# power.net
KiCad netlist of a schematic drawn in Altium Designer
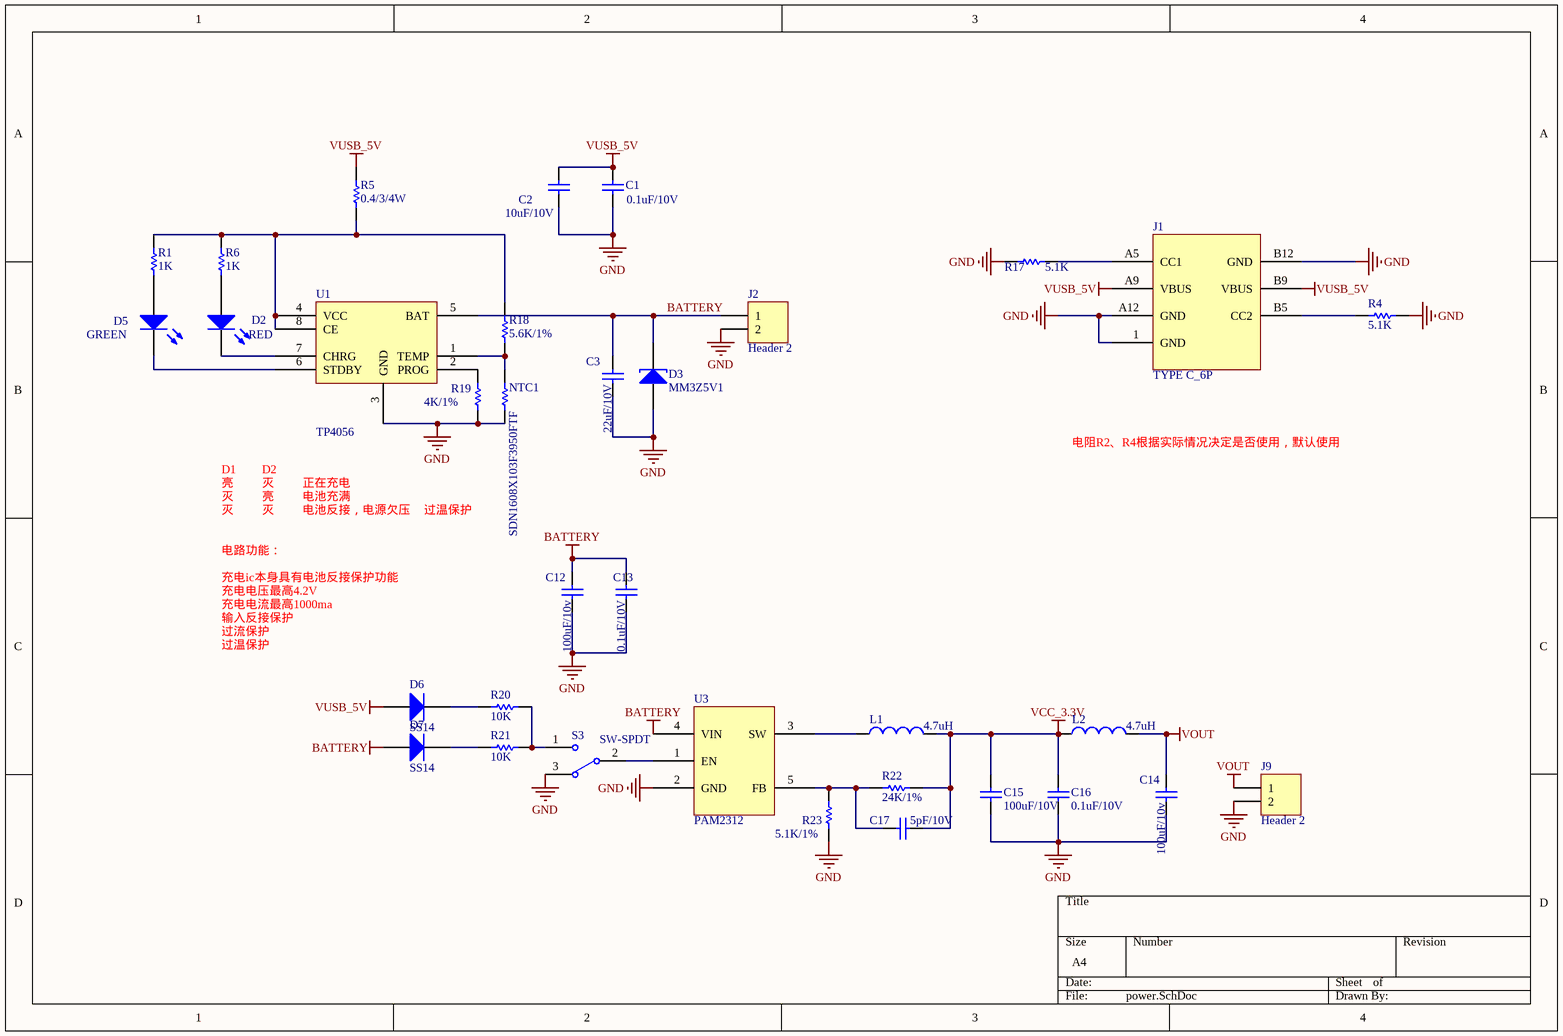
[diagram p0: power.SchDoc]

(export (version "E")
  (design (tool "Eeschema 10.0.6"))
  (components
    (comp (ref "C1")
      (value "0.1uF/10V")
      (footprint "0402C")
      (description "Capacitor")
      (fields (field (name "PUBLISHER") "Altium Limited"))
      (libsource (lib "Miscellaneous Devices") (part "Cap"))
    )
    (comp (ref "C2")
      (value "10uF/10V")
      (footprint "0603C")
      (description "Capacitor")
      (fields (field (name "PUBLISHER") "Altium Limited"))
      (libsource (lib "Miscellaneous Devices") (part "Cap"))
    )
    (comp (ref "C3")
      (value "22uF/10V")
      (footprint "1206C")
      (description "Capacitor")
      (fields (field (name "PUBLISHER") "Altium Limited"))
      (libsource (lib "Miscellaneous Devices") (part "Cap"))
    )
    (comp (ref "C12")
      (value "100uF/10v")
      (footprint "1206C")
      (description "Capacitor")
      (fields (field (name "PUBLISHER") "Altium Limited"))
      (libsource (lib "Miscellaneous Devices") (part "Cap"))
    )
    (comp (ref "C13")
      (value "0.1uF/10V")
      (footprint "0402c")
      (description "Capacitor")
      (fields (field (name "PUBLISHER") "Altium Limited"))
      (libsource (lib "Miscellaneous Devices") (part "Cap"))
    )
    (comp (ref "C14")
      (value "100uF/10v")
      (footprint "1206C")
      (description "Capacitor")
      (fields (field (name "PUBLISHER") "Altium Limited"))
      (libsource (lib "Miscellaneous Devices") (part "Cap"))
    )
    (comp (ref "C15")
      (value "100uF/10V")
      (footprint "1206C")
      (description "Capacitor")
      (fields (field (name "PUBLISHER") "Altium Limited"))
      (libsource (lib "Miscellaneous Devices") (part "Cap"))
    )
    (comp (ref "C16")
      (value "0.1uF/10V")
      (footprint "0402C")
      (description "Capacitor")
      (fields (field (name "PUBLISHER") "Altium Limited"))
      (libsource (lib "Miscellaneous Devices") (part "Cap"))
    )
    (comp (ref "C17")
      (value "5pF/10V")
      (footprint "0402C")
      (description "Capacitor")
      (fields (field (name "PUBLISHER") "Altium Limited"))
      (libsource (lib "Miscellaneous Devices") (part "Cap"))
    )
    (comp (ref "D2")
      (value "~")
      (footprint "0603LED")
      (description "Typical INFRARED GaAs LED")
      (fields (field (name "PUBLISHER") "RED"))
      (libsource (lib "Miscellaneous Devices") (part "LED0"))
    )
    (comp (ref "D3")
      (value "MM3Z5V1")
      (footprint "SOD323")
      (description "Tunnel Diode - RLC Model")
      (fields (field (name "PUBLISHER") "Altium Limited"))
      (libsource (lib "Miscellaneous Devices") (part "D Tunnel1"))
    )
    (comp (ref "D5")
      (value "~")
      (footprint "0603LED")
      (description "Typical INFRARED GaAs LED")
      (fields (field (name "PUBLISHER") "GREEN"))
      (libsource (lib "Miscellaneous Devices") (part "LED0"))
    )
    (comp (ref "D6")
      (value "SS14")
      (footprint "SMA")
      (description "Default Diode")
      (fields (field (name "PUBLISHER") "Altium Limited"))
      (libsource (lib "Miscellaneous Devices") (part "Diode"))
    )
    (comp (ref "D7")
      (value "SS14")
      (footprint "SMA")
      (description "Default Diode")
      (fields (field (name "PUBLISHER") "Altium Limited"))
      (libsource (lib "Miscellaneous Devices") (part "Diode"))
    )
    (comp (ref "J1")
      (value "TYPE C_6P")
      (footprint "TYPEC_6P")
      (libsource (lib "Schlib_20110825") (part "TYPE C_6P"))
    )
    (comp (ref "J2")
      (value "Header 2")
      (footprint "2X1.25MMW")
      (description "Header, 2-Pin")
      (fields (field (name "PUBLISHER") "Altium Limited"))
      (libsource (lib "Miscellaneous Connectors") (part "Header 2"))
    )
    (comp (ref "J9")
      (value "Header 2")
      (footprint "HDR1X2")
      (description "Header, 2-Pin")
      (fields (field (name "PUBLISHER") "Altium Limited"))
      (libsource (lib "Miscellaneous Connectors") (part "Header 2"))
    )
    (comp (ref "L1")
      (value "4.7uH")
      (footprint "0805r")
      (description "Inductor")
      (fields (field (name "PUBLISHER") "Altium Limited"))
      (libsource (lib "Miscellaneous Devices") (part "Inductor"))
    )
    (comp (ref "L2")
      (value "4.7uH")
      (footprint "0805r")
      (description "Inductor")
      (fields (field (name "PUBLISHER") "Altium Limited"))
      (libsource (lib "Miscellaneous Devices") (part "Inductor"))
    )
    (comp (ref "NTC1")
      (value "SDN1608X103F3950FTF")
      (footprint "0603R")
      (description "Semiconductor Resistor")
      (fields (field (name "PUBLISHER") "Altium Limited"))
      (libsource (lib "Miscellaneous Devices") (part "Res Semi"))
    )
    (comp (ref "R1")
      (value "1K")
      (footprint "0402R")
      (description "Semiconductor Resistor")
      (fields (field (name "PUBLISHER") "Altium Limited"))
      (libsource (lib "Miscellaneous Devices") (part "Res Semi"))
    )
    (comp (ref "R4")
      (value "5.1K")
      (footprint "0402R")
      (description "Semiconductor Resistor")
      (fields (field (name "PUBLISHER") "Altium Limited"))
      (libsource (lib "Miscellaneous Devices") (part "Res Semi"))
    )
    (comp (ref "R5")
      (value "0.4/3/4W")
      (footprint "2010R")
      (description "Semiconductor Resistor")
      (fields (field (name "PUBLISHER") "Altium Limited"))
      (libsource (lib "Miscellaneous Devices") (part "Res Semi"))
    )
    (comp (ref "R6")
      (value "1K")
      (footprint "0402R")
      (description "Semiconductor Resistor")
      (fields (field (name "PUBLISHER") "Altium Limited"))
      (libsource (lib "Miscellaneous Devices") (part "Res Semi"))
    )
    (comp (ref "R17")
      (value "5.1K")
      (footprint "0402R")
      (description "Semiconductor Resistor")
      (fields (field (name "PUBLISHER") "Altium Limited"))
      (libsource (lib "Miscellaneous Devices") (part "Res Semi"))
    )
    (comp (ref "R18")
      (value "5.6K/1%")
      (footprint "0402R")
      (description "Semiconductor Resistor")
      (fields (field (name "PUBLISHER") "Altium Limited"))
      (libsource (lib "Miscellaneous Devices") (part "Res Semi"))
    )
    (comp (ref "R19")
      (value "4K/1%")
      (footprint "0402R")
      (description "Semiconductor Resistor")
      (fields (field (name "PUBLISHER") "Altium Limited"))
      (libsource (lib "Miscellaneous Devices") (part "Res Semi"))
    )
    (comp (ref "R20")
      (value "10K")
      (footprint "0402R")
      (description "Semiconductor Resistor")
      (fields (field (name "PUBLISHER") "Altium Limited"))
      (libsource (lib "Miscellaneous Devices") (part "Res Semi"))
    )
    (comp (ref "R21")
      (value "10K")
      (footprint "0402R")
      (description "Semiconductor Resistor")
      (fields (field (name "PUBLISHER") "Altium Limited"))
      (libsource (lib "Miscellaneous Devices") (part "Res Semi"))
    )
    (comp (ref "R22")
      (value "24K/1%")
      (footprint "0402R")
      (description "Semiconductor Resistor")
      (fields (field (name "PUBLISHER") "Altium Limited"))
      (libsource (lib "Miscellaneous Devices") (part "Res Semi"))
    )
    (comp (ref "R23")
      (value "5.1K/1%")
      (footprint "0402R")
      (description "Semiconductor Resistor")
      (fields (field (name "PUBLISHER") "Altium Limited"))
      (libsource (lib "Miscellaneous Devices") (part "Res Semi"))
    )
    (comp (ref "S3")
      (value "SW-SPDT")
      (description "SPDT Subminiature Toggle Switch, Right Angle Mounting, Vertical Actuation")
      (fields (field (name "PUBLISHER") "Altium Limited"))
      (libsource (lib "Miscellaneous Devices") (part "SW-SPDT"))
    )
    (comp (ref "U1") (value "TP4056") (footprint "so-8") (libsource (lib "Schlib_20110825") (part "TP4056")))
    (comp (ref "U3")
      (value "PAM2312")
      (footprint "Pcblib_20110825:SOT-23-5")
      (libsource (lib "Schlib_20110825") (part "PAM2312"))
    )
  )
  (nets
    (net (code "1") (name "BATTERY") (class "Default")
      (node (ref "C12") (pin "1") (pinfunction "1_1") (pintype "passive"))
      (node (ref "C13") (pin "1") (pinfunction "1_1") (pintype "passive"))
      (node (ref "C3") (pin "1") (pinfunction "1_1") (pintype "passive"))
      (node (ref "D3") (pin "2") (pinfunction "K_2") (pintype "passive"))
      (node (ref "D7") (pin "1") (pinfunction "A_1") (pintype "passive"))
      (node (ref "J2") (pin "1") (pinfunction "1_1") (pintype "passive"))
      (node (ref "U1") (pin "5") (pinfunction "BAT_5") (pintype "passive"))
      (node (ref "U3") (pin "4") (pinfunction "VIN_4") (pintype "passive"))
    )
    (net (code "2") (name "GND") (class "Default")
      (node (ref "C1") (pin "1") (pinfunction "1_1") (pintype "passive"))
      (node (ref "C12") (pin "2") (pinfunction "2_2") (pintype "passive"))
      (node (ref "C13") (pin "2") (pinfunction "2_2") (pintype "passive"))
      (node (ref "C14") (pin "2") (pinfunction "2_2") (pintype "passive"))
      (node (ref "C15") (pin "1") (pinfunction "1_1") (pintype "passive"))
      (node (ref "C16") (pin "1") (pinfunction "1_1") (pintype "passive"))
      (node (ref "C2") (pin "1") (pinfunction "1_1") (pintype "passive"))
      (node (ref "C3") (pin "2") (pinfunction "2_2") (pintype "passive"))
      (node (ref "D3") (pin "1") (pinfunction "A_1") (pintype "passive"))
      (node (ref "J1") (pin "1") (pinfunction "GND_1") (pintype "passive"))
      (node (ref "J1") (pin "A12") (pinfunction "GND_A12") (pintype "passive"))
      (node (ref "J1") (pin "B12") (pinfunction "GND_B12") (pintype "passive"))
      (node (ref "J2") (pin "2") (pinfunction "2_2") (pintype "passive"))
      (node (ref "J9") (pin "2") (pinfunction "2_2") (pintype "passive"))
      (node (ref "NTC1") (pin "2") (pinfunction "2_2") (pintype "passive"))
      (node (ref "R17") (pin "2") (pinfunction "2_2") (pintype "passive"))
      (node (ref "R19") (pin "1") (pinfunction "1_1") (pintype "passive"))
      (node (ref "R23") (pin "1") (pinfunction "1_1") (pintype "passive"))
      (node (ref "R4") (pin "2") (pinfunction "2_2") (pintype "passive"))
      (node (ref "S3") (pin "3") (pinfunction "3_3") (pintype "passive"))
      (node (ref "U1") (pin "3") (pinfunction "GND_3") (pintype "passive"))
      (node (ref "U3") (pin "2") (pinfunction "GND_2") (pintype "passive"))
    )
    (net (code "3") (name "Net-(D2-A)") (class "Default")
      (node (ref "D2") (pin "1") (pinfunction "A_1") (pintype "passive"))
      (node (ref "R6") (pin "1") (pinfunction "1_1") (pintype "passive"))
    )
    (net (code "4") (name "Net-(D2-K)") (class "Default")
      (node (ref "D2") (pin "2") (pinfunction "K_2") (pintype "passive"))
      (node (ref "U1") (pin "7") (pinfunction "CHRG_7") (pintype "passive"))
    )
    (net (code "5") (name "Net-(D5-A)") (class "Default")
      (node (ref "D5") (pin "1") (pinfunction "A_1") (pintype "passive"))
      (node (ref "R1") (pin "1") (pinfunction "1_1") (pintype "passive"))
    )
    (net (code "6") (name "Net-(D5-K)") (class "Default")
      (node (ref "D5") (pin "2") (pinfunction "K_2") (pintype "passive"))
      (node (ref "U1") (pin "6") (pinfunction "STDBY_6") (pintype "passive"))
    )
    (net (code "7") (name "Net-(D6-K)") (class "Default")
      (node (ref "D6") (pin "2") (pinfunction "K_2") (pintype "passive"))
      (node (ref "R20") (pin "1") (pinfunction "1_1") (pintype "passive"))
    )
    (net (code "8") (name "Net-(D7-K)") (class "Default")
      (node (ref "D7") (pin "2") (pinfunction "K_2") (pintype "passive"))
      (node (ref "R21") (pin "1") (pinfunction "1_1") (pintype "passive"))
    )
    (net (code "9") (name "Net-(J1-CC1)") (class "Default")
      (node (ref "J1") (pin "A5") (pinfunction "CC1_A5") (pintype "passive"))
      (node (ref "R17") (pin "1") (pinfunction "1_1") (pintype "passive"))
    )
    (net (code "10") (name "Net-(J1-CC2)") (class "Default")
      (node (ref "J1") (pin "B5") (pinfunction "CC2_B5") (pintype "passive"))
      (node (ref "R4") (pin "1") (pinfunction "1_1") (pintype "passive"))
    )
    (net (code "11") (name "Net-(R20-Pad2)") (class "Default")
      (node (ref "R20") (pin "2") (pinfunction "2_2") (pintype "passive"))
      (node (ref "R21") (pin "2") (pinfunction "2_2") (pintype "passive"))
      (node (ref "S3") (pin "1") (pinfunction "1_1") (pintype "passive"))
    )
    (net (code "12") (name "Net-(U1-CE)") (class "Default")
      (node (ref "R1") (pin "2") (pinfunction "2_2") (pintype "passive"))
      (node (ref "R18") (pin "1") (pinfunction "1_1") (pintype "passive"))
      (node (ref "R5") (pin "2") (pinfunction "2_2") (pintype "passive"))
      (node (ref "R6") (pin "2") (pinfunction "2_2") (pintype "passive"))
      (node (ref "U1") (pin "4") (pinfunction "VCC_4") (pintype "passive"))
      (node (ref "U1") (pin "8") (pinfunction "CE_8") (pintype "passive"))
    )
    (net (code "13") (name "Net-(U1-PROG)") (class "Default")
      (node (ref "R19") (pin "2") (pinfunction "2_2") (pintype "passive"))
      (node (ref "U1") (pin "2") (pinfunction "PROG_2") (pintype "passive"))
    )
    (net (code "14") (name "Net-(U1-TEMP)") (class "Default")
      (node (ref "NTC1") (pin "1") (pinfunction "1_1") (pintype "passive"))
      (node (ref "R18") (pin "2") (pinfunction "2_2") (pintype "passive"))
      (node (ref "U1") (pin "1") (pinfunction "TEMP_1") (pintype "passive"))
    )
    (net (code "15") (name "Net-(U3-EN)") (class "Default")
      (node (ref "S3") (pin "2") (pinfunction "2_2") (pintype "passive"))
      (node (ref "U3") (pin "1") (pinfunction "EN_1") (pintype "passive"))
    )
    (net (code "16") (name "Net-(U3-FB)") (class "Default")
      (node (ref "C17") (pin "1") (pinfunction "1_1") (pintype "passive"))
      (node (ref "R22") (pin "1") (pinfunction "1_1") (pintype "passive"))
      (node (ref "R23") (pin "2") (pinfunction "2_2") (pintype "passive"))
      (node (ref "U3") (pin "5") (pinfunction "FB_5") (pintype "passive"))
    )
    (net (code "17") (name "Net-(U3-SW)") (class "Default")
      (node (ref "L1") (pin "1") (pinfunction "1_1") (pintype "passive"))
      (node (ref "U3") (pin "3") (pinfunction "SW_3") (pintype "passive"))
    )
    (net (code "18") (name "VCC_3.3V") (class "Default")
      (node (ref "C15") (pin "2") (pinfunction "2_2") (pintype "passive"))
      (node (ref "C16") (pin "2") (pinfunction "2_2") (pintype "passive"))
      (node (ref "C17") (pin "2") (pinfunction "2_2") (pintype "passive"))
      (node (ref "L1") (pin "2") (pinfunction "2_2") (pintype "passive"))
      (node (ref "L2") (pin "1") (pinfunction "1_1") (pintype "passive"))
      (node (ref "R22") (pin "2") (pinfunction "2_2") (pintype "passive"))
    )
    (net (code "19") (name "VOUT") (class "Default")
      (node (ref "C14") (pin "1") (pinfunction "1_1") (pintype "passive"))
      (node (ref "J9") (pin "1") (pinfunction "1_1") (pintype "passive"))
      (node (ref "L2") (pin "2") (pinfunction "2_2") (pintype "passive"))
    )
    (net (code "20") (name "VUSB_5V") (class "Default")
      (node (ref "C1") (pin "2") (pinfunction "2_2") (pintype "passive"))
      (node (ref "C2") (pin "2") (pinfunction "2_2") (pintype "passive"))
      (node (ref "D6") (pin "1") (pinfunction "A_1") (pintype "passive"))
      (node (ref "J1") (pin "A9") (pinfunction "VBUS_A9") (pintype "passive"))
      (node (ref "J1") (pin "B9") (pinfunction "VBUS_B9") (pintype "passive"))
      (node (ref "R5") (pin "1") (pinfunction "1_1") (pintype "passive"))
    )
  )
)
